# original_schematic.net
KiCad netlist of a schematic drawn in Altium Designer
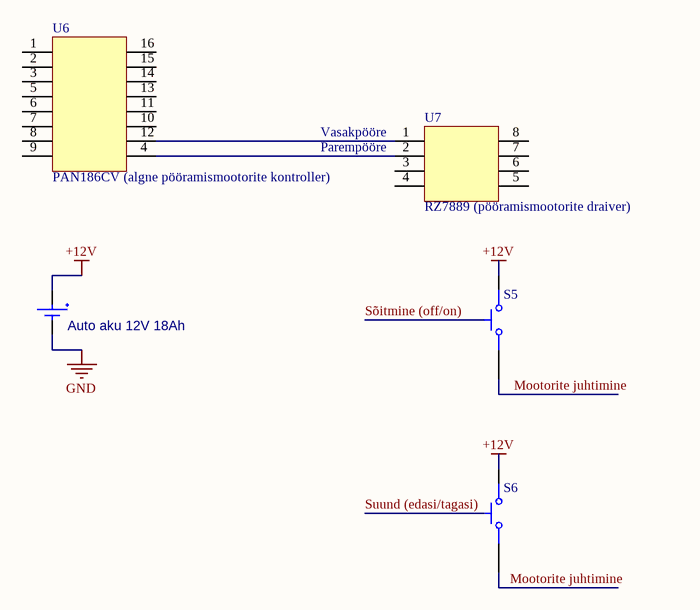
[diagram p0: original_schematic.SchDoc]

(export (version "E")
  (design (tool "Eeschema 10.0.6"))
  (components
    (comp (ref "Auto aku 12V 18Ah")
      (value "~")
      (footprint "SEIK-MS621FE-FL11E-2_V")
      (description "MS Lihium Rechargeable Battery, 3 V, -20 to 60 degC, Tray")
      (libsource (lib "Kaisa Talts") (part "CMP-00622-2"))
    )
    (comp (ref "S5")
      (value "~")
      (footprint "OMRON-B3U-1000_V")
      (description "Tactile Switch, SPST-NO, 0.05 A, 12 V, -25 to 70 degC, 2-Pin SMD, RoHS, Tape and Reel")
      (fields (field (name "MANUFACTURER") "Omron Electronic Components"))
      (libsource (lib "Kaisa Talts") (part "SW-SPST-NO-2"))
    )
    (comp (ref "S6")
      (value "~")
      (footprint "OMRON-B3U-1000_V")
      (description "Tactile Switch, SPST-NO, 0.05 A, 12 V, -25 to 70 degC, 2-Pin SMD, RoHS, Tape and Reel")
      (fields (field (name "MANUFACTURER") "Omron Electronic Components"))
      (libsource (lib "Kaisa Talts") (part "SW-SPST-NO-2"))
    )
    (comp (ref "U6")
      (value "PAN186CV (algne pööramismootorite kontroller)")
      (libsource (lib "Kaisa Talts") (part "PAN186CV"))
    )
    (comp (ref "U7")
      (value "RZ7889 (pööramismootorite draiver)")
      (libsource (lib "Kaisa Talts") (part "RZ7889"))
    )
  )
  (nets
    (net (code "1") (name "+12V") (class "Default")
      (node (ref "Auto aku 12V 18Ah") (pin "1") (pinfunction "+_1") (pintype "passive"))
      (node (ref "S5") (pin "2") (pinfunction "2_2") (pintype "passive"))
      (node (ref "S6") (pin "2") (pinfunction "2_2") (pintype "passive"))
    )
    (net (code "2") (name "/Mootorite juhtimine") (class "Default")
      (node (ref "S5") (pin "1") (pinfunction "1_1") (pintype "passive"))
      (node (ref "S6") (pin "1") (pinfunction "1_1") (pintype "passive"))
    )
    (net (code "5") (name "GND") (class "Default")
      (node (ref "Auto aku 12V 18Ah") (pin "2") (pinfunction "-_2") (pintype "passive"))
    )
    (net (code "6") (name "Net-(U6-Pad4)") (class "Default")
      (node (ref "U6") (pin "4") (pintype "passive"))
      (node (ref "U7") (pin "2") (pintype "passive"))
    )
    (net (code "7") (name "Net-(U6-Pad12)") (class "Default")
      (node (ref "U6") (pin "12") (pintype "passive"))
      (node (ref "U7") (pin "1") (pintype "passive"))
    )
    (net (code "8") (name "unconnected-(U6-Pad1)") (class "Default")
      (node (ref "U6") (pin "1") (pintype "passive"))
    )
    (net (code "9") (name "unconnected-(U6-Pad2)") (class "Default")
      (node (ref "U6") (pin "2") (pintype "passive"))
    )
    (net (code "10") (name "unconnected-(U6-Pad3)") (class "Default")
      (node (ref "U6") (pin "3") (pintype "passive"))
    )
    (net (code "11") (name "unconnected-(U6-Pad5)") (class "Default")
      (node (ref "U6") (pin "5") (pintype "passive"))
    )
    (net (code "12") (name "unconnected-(U6-Pad6)") (class "Default")
      (node (ref "U6") (pin "6") (pintype "passive"))
    )
    (net (code "13") (name "unconnected-(U6-Pad7)") (class "Default")
      (node (ref "U6") (pin "7") (pintype "passive"))
    )
    (net (code "14") (name "unconnected-(U6-Pad8)") (class "Default")
      (node (ref "U6") (pin "8") (pintype "passive"))
    )
    (net (code "15") (name "unconnected-(U6-Pad9)") (class "Default")
      (node (ref "U6") (pin "9") (pintype "passive"))
    )
    (net (code "16") (name "unconnected-(U6-Pad10)") (class "Default")
      (node (ref "U6") (pin "10") (pintype "passive"))
    )
    (net (code "17") (name "unconnected-(U6-Pad11)") (class "Default")
      (node (ref "U6") (pin "11") (pintype "passive"))
    )
    (net (code "18") (name "unconnected-(U6-Pad13)") (class "Default")
      (node (ref "U6") (pin "13") (pintype "passive"))
    )
    (net (code "19") (name "unconnected-(U6-Pad14)") (class "Default")
      (node (ref "U6") (pin "14") (pintype "passive"))
    )
    (net (code "20") (name "unconnected-(U6-Pad15)") (class "Default")
      (node (ref "U6") (pin "15") (pintype "passive"))
    )
    (net (code "21") (name "unconnected-(U6-Pad16)") (class "Default")
      (node (ref "U6") (pin "16") (pintype "passive"))
    )
    (net (code "22") (name "unconnected-(U7-Pad3)") (class "Default")
      (node (ref "U7") (pin "3") (pintype "passive"))
    )
    (net (code "23") (name "unconnected-(U7-Pad4)") (class "Default")
      (node (ref "U7") (pin "4") (pintype "passive"))
    )
    (net (code "24") (name "unconnected-(U7-Pad5)") (class "Default")
      (node (ref "U7") (pin "5") (pintype "passive"))
    )
    (net (code "25") (name "unconnected-(U7-Pad6)") (class "Default")
      (node (ref "U7") (pin "6") (pintype "passive"))
    )
    (net (code "26") (name "unconnected-(U7-Pad7)") (class "Default")
      (node (ref "U7") (pin "7") (pintype "passive"))
    )
    (net (code "27") (name "unconnected-(U7-Pad8)") (class "Default")
      (node (ref "U7") (pin "8") (pintype "passive"))
    )
  )
)
